# EDU_High-Speed-Design_CPU_USB.net
KiCad netlist of a schematic drawn in Altium Designer
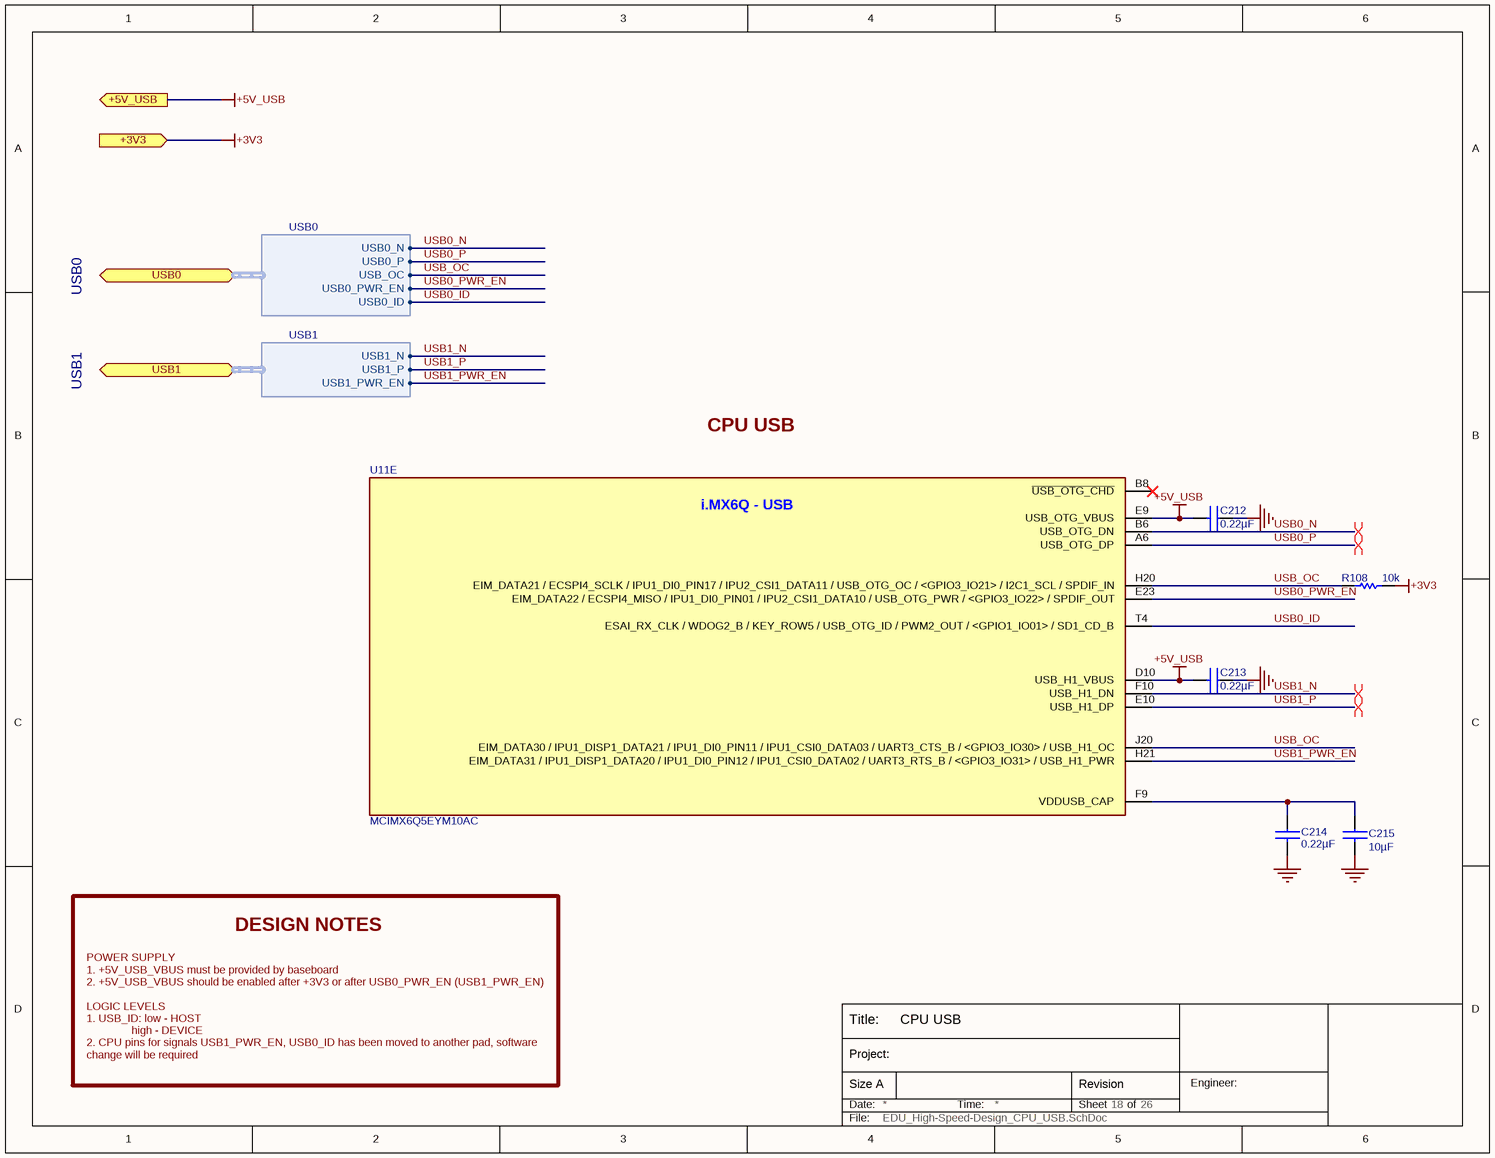
[diagram p0: EDU_High-Speed-Design_CPU_USB.SchDoc]

(export (version "E")
  (design (tool "Eeschema 10.0.6"))
  (components
    (comp (ref "C212")
      (value "0.22µF")
      (footprint "C0402")
      (description "CAP CER .22UF 25V X5R 20% 0402")
      (fields (field (name "VOLTAGE") "25V"))
      (libsource (lib "EDU_High-Speed-Design") (part "C1005X5R1E224M"))
    )
    (comp (ref "C213")
      (value "0.22µF")
      (footprint "C0402")
      (description "CAP CER .22UF 25V X5R 20% 0402")
      (fields (field (name "VOLTAGE") "25V"))
      (libsource (lib "EDU_High-Speed-Design") (part "C1005X5R1E224M"))
    )
    (comp (ref "C214")
      (value "0.22µF")
      (footprint "C0402")
      (description "CAP CER .22UF 25V X5R 20% 0402")
      (fields (field (name "VOLTAGE") "25V"))
      (libsource (lib "EDU_High-Speed-Design") (part "C1005X5R1E224M"))
    )
    (comp (ref "C215")
      (value "10µF")
      (footprint "C0603")
      (description "CAP CER 10UF 6.3V X5R 20% 0603")
      (fields (field (name "VOLTAGE") "6.3V"))
      (libsource (lib "EDU_High-Speed-Design") (part "C1608X5R0J106M"))
    )
    (comp (ref "R108")
      (value "10k")
      (footprint "R0402")
      (description "RES 10.0K OHM 1/16W 1% 0402 SMD")
      (libsource (lib "EDU_High-Speed-Design") (part "RC0402FR-0710KL"))
    )
    (comp (ref "U11")
      (value "MCIMX6Q5EYM10AC")
      (footprint "MCIMX6Q5EYM10AC")
      (description "IC MCU 32BIT ARM QUAD 624FCBGA")
      (libsource (lib "EDU_High-Speed-Design") (part "MCIMX6Q5EYM10AC"))
    )
  )
  (nets
    (net (code "3") (name "+3V3") (class "Default")
      (node (ref "R108") (pin "2") (pinfunction "2_2") (pintype "passive"))
    )
    (net (code "4") (name "+5V_USB") (class "Default")
      (node (ref "C212") (pin "2") (pinfunction "2_2") (pintype "passive"))
      (node (ref "C213") (pin "2") (pinfunction "2_2") (pintype "passive"))
      (node (ref "U11") (pin "D10") (pinfunction "USB_H1_VBUS_D10") (pintype "passive"))
      (node (ref "U11") (pin "E9") (pinfunction "USB_OTG_VBUS_E9") (pintype "passive"))
    )
    (net (code "5") (name "/USB0_ID") (class "Default")
      (node (ref "U11") (pin "T4") (pinfunction "ESAI_RX_CLK_/_WDOG2_B_/_KEY_ROW5_/_USB_OTG_ID_/_PWM2_OUT_/_<GPIO1_IO01>_/_SD1_CD_B_T4") (pintype "passive"))
    )
    (net (code "6") (name "/USB0_N") (class "Default")
      (node (ref "U11") (pin "B6") (pinfunction "USB_OTG_DN_B6") (pintype "passive"))
    )
    (net (code "7") (name "/USB0_P") (class "Default")
      (node (ref "U11") (pin "A6") (pinfunction "USB_OTG_DP_A6") (pintype "passive"))
    )
    (net (code "8") (name "/USB0_PWR_EN") (class "Default")
      (node (ref "U11") (pin "E23") (pinfunction "EIM_DATA22_/_ECSPI4_MISO_/_IPU1_DI0_PIN01_/_IPU2_CSI1_DATA10_/_USB_OTG_PWR_/_<GPIO3_IO22>_/_SPDIF_OUT_E23") (pintype "passive"))
    )
    (net (code "9") (name "/USB1_N") (class "Default")
      (node (ref "U11") (pin "F10") (pinfunction "USB_H1_DN_F10") (pintype "passive"))
    )
    (net (code "10") (name "/USB1_P") (class "Default")
      (node (ref "U11") (pin "E10") (pinfunction "USB_H1_DP_E10") (pintype "passive"))
    )
    (net (code "11") (name "/USB1_PWR_EN") (class "Default")
      (node (ref "U11") (pin "H21") (pinfunction "EIM_DATA31_/_IPU1_DISP1_DATA20_/_IPU1_DI0_PIN12_/_IPU1_CSI0_DATA02_/_UART3_RTS_B_/_<GPIO3_IO31>_/_USB_H1_PWR_H21") (pintype "passive"))
    )
    (net (code "12") (name "/USB_OC") (class "Default")
      (node (ref "R108") (pin "1") (pinfunction "1_1") (pintype "passive"))
      (node (ref "U11") (pin "H20") (pinfunction "EIM_DATA21_/_ECSPI4_SCLK_/_IPU1_DI0_PIN17_/_IPU2_CSI1_DATA11_/_USB_OTG_OC_/_<GPIO3_IO21>_/_I2C1_SCL_/_SPDIF_IN_H20") (pintype "passive"))
      (node (ref "U11") (pin "J20") (pinfunction "EIM_DATA30_/_IPU1_DISP1_DATA21_/_IPU1_DI0_PIN11_/_IPU1_CSI0_DATA03_/_UART3_CTS_B_/_<GPIO3_IO30>_/_USB_H1_OC_J20") (pintype "passive"))
    )
    (net (code "15") (name "GND") (class "Default")
      (node (ref "C212") (pin "1") (pinfunction "1_1") (pintype "passive"))
      (node (ref "C213") (pin "1") (pinfunction "1_1") (pintype "passive"))
      (node (ref "C214") (pin "2") (pinfunction "2_2") (pintype "passive"))
      (node (ref "C215") (pin "2") (pinfunction "2_2") (pintype "passive"))
    )
    (net (code "16") (name "Net-(U11E-VDDUSB_CAP)") (class "Default")
      (node (ref "C214") (pin "1") (pinfunction "1_1") (pintype "passive"))
      (node (ref "C215") (pin "1") (pinfunction "1_1") (pintype "passive"))
      (node (ref "U11") (pin "F9") (pinfunction "VDDUSB_CAP_F9") (pintype "passive"))
    )
    (net (code "17") (name "unconnected-(U11E-~{USB_OTG_CHD}-PadB8)") (class "Default")
      (node (ref "U11") (pin "B8") (pinfunction "~{USB_OTG_CHD}_B8") (pintype "passive+no_connect"))
    )
  )
)
